# optiboard.net
KiCad netlist of a schematic drawn in EAGLE
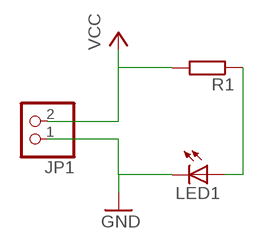
[diagram p0: schematic, sheet 1]

(export (version "E")
  (design (tool "Eeschema 10.0.6"))
  (components
    (comp (ref "JP1")
      (value "PINHD-1X2")
      (footprint "eagle-import:1X02")
      (libsource (lib "eagle-import") (part "PINHD-1X2"))
    )
    (comp (ref "LED1")
      (value "LED3MM")
      (footprint "eagle-import:LED3MM")
      (libsource (lib "eagle-import") (part "LED3MM"))
    )
    (comp (ref "R1")
      (value "R-EU_0207/10")
      (footprint "eagle-import:0207_10")
      (libsource (lib "eagle-import") (part "R-EU_0207/10"))
    )
  )
  (nets
    (net (code "1") (name "GND") (class "Default")
      (node (ref "JP1") (pin "1") (pinfunction "1_1") (pintype "passive"))
      (node (ref "LED1") (pin "K") (pinfunction "C_K") (pintype "passive"))
    )
    (net (code "2") (name "Net-(LED1-PadA)") (class "Default")
      (node (ref "LED1") (pin "A") (pinfunction "A_A") (pintype "passive"))
      (node (ref "R1") (pin "1") (pinfunction "1_1") (pintype "passive"))
    )
    (net (code "3") (name "VCC") (class "Default")
      (node (ref "JP1") (pin "2") (pinfunction "2_2") (pintype "passive"))
      (node (ref "R1") (pin "2") (pinfunction "2_2") (pintype "passive"))
    )
  )
)
